# MODULES.net
KiCad netlist of a schematic drawn in Altium Designer
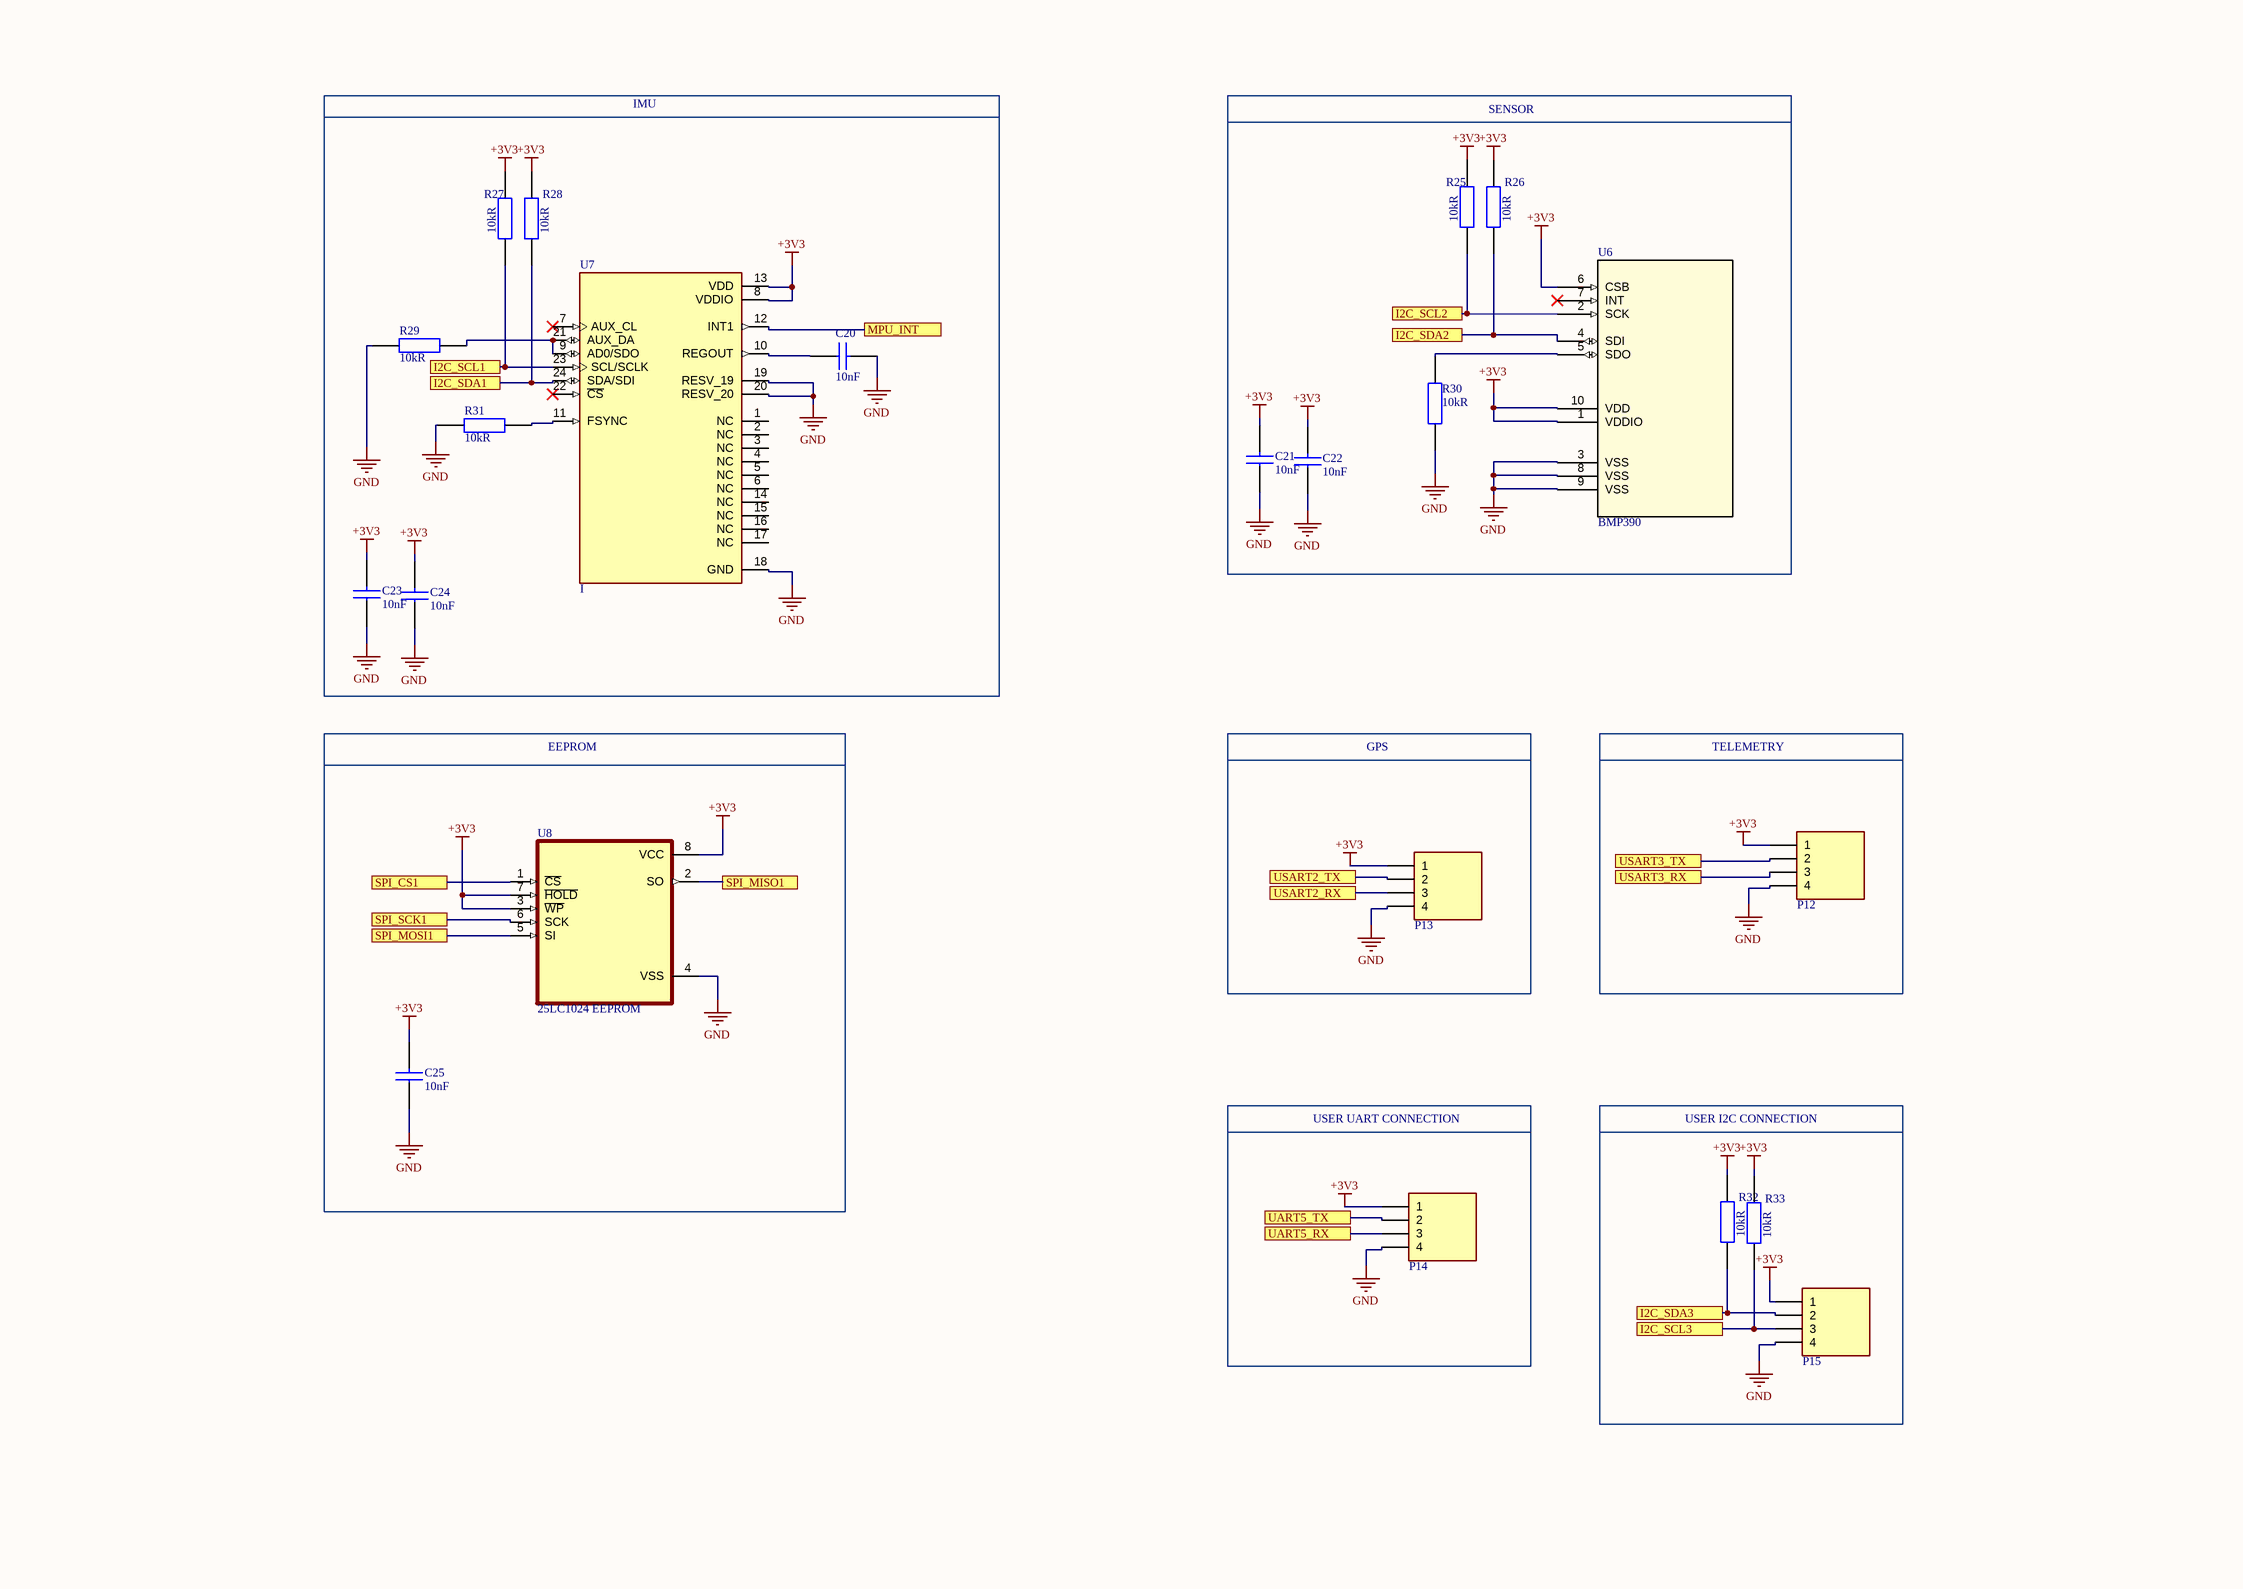
[diagram p0: MODULES.SchDoc]

(export (version "E")
  (design (tool "Eeschema 10.0.6"))
  (components
    (comp (ref "C20")
      (value "0603B103K160CT")
      (footprint "CAP_0603")
      (description "CAP CER 10nF %10 0603")
      (fields
        (field (name "MANUFACTURER") "Walsin Technologies")
        (field (name "TOLERANCE") "10%")
        (field (name "CAPACITANCE") "10nF")
        (field (name "DESIGNED BY") "BERK")
      )
      (libsource (lib "UDEMY_Library") (part "CAP CER 10nF 0603"))
    )
    (comp (ref "C21")
      (value "0603B103K160CT")
      (footprint "CAP_0603")
      (description "CAP CER 10nF %10 0603")
      (fields
        (field (name "MANUFACTURER") "Walsin Technologies")
        (field (name "TOLERANCE") "10%")
        (field (name "CAPACITANCE") "10nF")
        (field (name "DESIGNED BY") "BERK")
      )
      (libsource (lib "UDEMY_Library") (part "CAP CER 10nF 0603"))
    )
    (comp (ref "C22")
      (value "0603B103K160CT")
      (footprint "CAP_0603")
      (description "CAP CER 10nF %10 0603")
      (fields
        (field (name "MANUFACTURER") "Walsin Technologies")
        (field (name "TOLERANCE") "10%")
        (field (name "CAPACITANCE") "10nF")
        (field (name "DESIGNED BY") "BERK")
      )
      (libsource (lib "UDEMY_Library") (part "CAP CER 10nF 0603"))
    )
    (comp (ref "C23")
      (value "0603B103K160CT")
      (footprint "CAP_0603")
      (description "CAP CER 10nF %10 0603")
      (fields
        (field (name "MANUFACTURER") "Walsin Technologies")
        (field (name "TOLERANCE") "10%")
        (field (name "CAPACITANCE") "10nF")
        (field (name "DESIGNED BY") "BERK")
      )
      (libsource (lib "UDEMY_Library") (part "CAP CER 10nF 0603"))
    )
    (comp (ref "C24")
      (value "0603B103K160CT")
      (footprint "CAP_0603")
      (description "CAP CER 10nF %10 0603")
      (fields
        (field (name "MANUFACTURER") "Walsin Technologies")
        (field (name "TOLERANCE") "10%")
        (field (name "CAPACITANCE") "10nF")
        (field (name "DESIGNED BY") "BERK")
      )
      (libsource (lib "UDEMY_Library") (part "CAP CER 10nF 0603"))
    )
    (comp (ref "C25")
      (value "0603B103K160CT")
      (footprint "CAP_0603")
      (description "CAP CER 10nF %10 0603")
      (fields
        (field (name "MANUFACTURER") "Walsin Technologies")
        (field (name "TOLERANCE") "10%")
        (field (name "CAPACITANCE") "10nF")
        (field (name "DESIGNED BY") "BERK")
      )
      (libsource (lib "UDEMY_Library") (part "CAP CER 10nF 0603"))
    )
    (comp (ref "P12")
      (value "HEADER 4 PIN")
      (footprint "S4B-XH-A")
      (description "Header, Right Angle, 4Way; ¦Jst / Japan Solderless Terminals S4B-XH-A (LF)(SN)")
      (fields
        (field (name "MANUFACTURER") "JST")
        (field (name "MANUFACTURER PART NUMBER") "S4B-XH-A(LF)(SN)")
      )
      (libsource (lib "Main_Library") (part "HEADER 4 PIN"))
    )
    (comp (ref "P13")
      (value "HEADER 4 PIN")
      (footprint "S4B-XH-A")
      (description "Header, Right Angle, 4Way; ¦Jst / Japan Solderless Terminals S4B-XH-A (LF)(SN)")
      (fields
        (field (name "MANUFACTURER") "JST")
        (field (name "MANUFACTURER PART NUMBER") "S4B-XH-A(LF)(SN)")
      )
      (libsource (lib "Main_Library") (part "HEADER 4 PIN"))
    )
    (comp (ref "P14")
      (value "HEADER 4 PIN")
      (footprint "S4B-XH-A")
      (description "Header, Right Angle, 4Way; ¦Jst / Japan Solderless Terminals S4B-XH-A (LF)(SN)")
      (fields
        (field (name "MANUFACTURER") "JST")
        (field (name "MANUFACTURER PART NUMBER") "S4B-XH-A(LF)(SN)")
      )
      (libsource (lib "Main_Library") (part "HEADER 4 PIN"))
    )
    (comp (ref "P15")
      (value "HEADER 4 PIN")
      (footprint "S4B-XH-A")
      (description "Header, Right Angle, 4Way; ¦Jst / Japan Solderless Terminals S4B-XH-A (LF)(SN)")
      (fields
        (field (name "MANUFACTURER") "JST")
        (field (name "MANUFACTURER PART NUMBER") "S4B-XH-A(LF)(SN)")
      )
      (libsource (lib "Main_Library") (part "HEADER 4 PIN"))
    )
    (comp (ref "R25")
      (value "RC0603FR-0710KL")
      (footprint "RES_0603")
      (description "RES 10K %1 OHM 0603 SMD")
      (fields
        (field (name "MANUFACTURER") "Yageo")
        (field (name "TOLERANCE") "1%")
        (field (name "RESISTANCE") "10kR")
        (field (name "DESIGNED BY") "BERK")
      )
      (libsource (lib "UDEMY_Library") (part "RES 10K OHM 0603"))
    )
    (comp (ref "R26")
      (value "RC0603FR-0710KL")
      (footprint "RES_0603")
      (description "RES 10K %1 OHM 0603 SMD")
      (fields
        (field (name "MANUFACTURER") "Yageo")
        (field (name "TOLERANCE") "1%")
        (field (name "RESISTANCE") "10kR")
        (field (name "DESIGNED BY") "BERK")
      )
      (libsource (lib "UDEMY_Library") (part "RES 10K OHM 0603"))
    )
    (comp (ref "R27")
      (value "RC0603FR-0710KL")
      (footprint "RES_0603")
      (description "RES 10K %1 OHM 0603 SMD")
      (fields
        (field (name "MANUFACTURER") "Yageo")
        (field (name "TOLERANCE") "1%")
        (field (name "RESISTANCE") "10kR")
        (field (name "DESIGNED BY") "BERK")
      )
      (libsource (lib "UDEMY_Library") (part "RES 10K OHM 0603"))
    )
    (comp (ref "R28")
      (value "RC0603FR-0710KL")
      (footprint "RES_0603")
      (description "RES 10K %1 OHM 0603 SMD")
      (fields
        (field (name "MANUFACTURER") "Yageo")
        (field (name "TOLERANCE") "1%")
        (field (name "RESISTANCE") "10kR")
        (field (name "DESIGNED BY") "BERK")
      )
      (libsource (lib "UDEMY_Library") (part "RES 10K OHM 0603"))
    )
    (comp (ref "R29")
      (value "RC0603FR-0710KL")
      (footprint "RES_0603")
      (description "RES 10K %1 OHM 0603 SMD")
      (fields
        (field (name "MANUFACTURER") "Yageo")
        (field (name "TOLERANCE") "1%")
        (field (name "RESISTANCE") "10kR")
        (field (name "DESIGNED BY") "BERK")
      )
      (libsource (lib "") (part "RES 10K OHM 0603_1"))
    )
    (comp (ref "R30")
      (value "RC0603FR-0710KL")
      (footprint "RES_0603")
      (description "RES 10K %1 OHM 0603 SMD")
      (fields
        (field (name "MANUFACTURER") "Yageo")
        (field (name "TOLERANCE") "1%")
        (field (name "RESISTANCE") "10kR")
        (field (name "DESIGNED BY") "BERK")
      )
      (libsource (lib "UDEMY_Library") (part "RES 10K OHM 0603"))
    )
    (comp (ref "R31")
      (value "RC0603FR-0710KL")
      (footprint "RES_0603")
      (description "RES 10K %1 OHM 0603 SMD")
      (fields
        (field (name "MANUFACTURER") "Yageo")
        (field (name "TOLERANCE") "1%")
        (field (name "RESISTANCE") "10kR")
        (field (name "DESIGNED BY") "BERK")
      )
      (libsource (lib "") (part "RES 10K OHM 0603_1"))
    )
    (comp (ref "R32")
      (value "RC0603FR-0710KL")
      (footprint "RES_0603")
      (description "RES 10K %1 OHM 0603 SMD")
      (fields
        (field (name "MANUFACTURER") "Yageo")
        (field (name "TOLERANCE") "1%")
        (field (name "RESISTANCE") "10kR")
        (field (name "DESIGNED BY") "BERK")
      )
      (libsource (lib "UDEMY_Library") (part "RES 10K OHM 0603"))
    )
    (comp (ref "R33")
      (value "RC0603FR-0710KL")
      (footprint "RES_0603")
      (description "RES 10K %1 OHM 0603 SMD")
      (fields
        (field (name "MANUFACTURER") "Yageo")
        (field (name "TOLERANCE") "1%")
        (field (name "RESISTANCE") "10kR")
        (field (name "DESIGNED BY") "BERK")
      )
      (libsource (lib "UDEMY_Library") (part "RES 10K OHM 0603"))
    )
    (comp (ref "U6")
      (value "BMP390")
      (footprint "WFLGA-10")
      (description "3.0 Shuttle Board Dev Kit BMP390")
      (fields
        (field (name "MANUFACTURER") "Bosch Sensortec")
        (field (name "MANUFACTURER PART NUMBER") "SHUTTLE BOARD 3.0 BMP390")
      )
      (libsource (lib "Main_Library") (part "BMP390"))
    )
    (comp (ref "U7")
      (value "I")
      (footprint "TFQFN-24")
      (description "IMU (Inertial Measurement Unit), 9-Axis, Accelerometer, Gyroscope, Compass")
      (fields (field (name "MANUFACTURER") "TDK") (field (name "MANUFACTURER PART NUMBER") "ICM-20948"))
      (libsource (lib "Main_Library") (part "ICM-20948"))
    )
    (comp (ref "U8")
      (value "25LC1024 EEPROM")
      (footprint "SOIJ8")
      (description "SPI Serial EEPROM Family, 8-bit, 20 MHz, 2.5 to 5.5V, -40°Cto 125°C, SOIJ-8, RoHS")
      (fields
        (field (name "MANUFACTURER") "Microchip")
        (field (name "MANUFACTURER PART NUMBER") "25LC1024-E/SM")
      )
      (libsource (lib "Main_Library") (part "25LC1024 EEPROM"))
    )
  )
  (nets
    (net (code "1") (name "+3V3") (class "Default")
      (node (ref "C21") (pin "2") (pinfunction "2_2") (pintype "passive"))
      (node (ref "C22") (pin "2") (pinfunction "2_2") (pintype "passive"))
      (node (ref "C23") (pin "2") (pinfunction "2_2") (pintype "passive"))
      (node (ref "C24") (pin "2") (pinfunction "2_2") (pintype "passive"))
      (node (ref "C25") (pin "2") (pinfunction "2_2") (pintype "passive"))
      (node (ref "P12") (pin "1") (pinfunction "1_1") (pintype "passive"))
      (node (ref "P13") (pin "1") (pinfunction "1_1") (pintype "passive"))
      (node (ref "P14") (pin "1") (pinfunction "1_1") (pintype "passive"))
      (node (ref "P15") (pin "1") (pinfunction "1_1") (pintype "passive"))
      (node (ref "R25") (pin "2") (pinfunction "2_2") (pintype "passive"))
      (node (ref "R26") (pin "2") (pinfunction "2_2") (pintype "passive"))
      (node (ref "R27") (pin "2") (pinfunction "2_2") (pintype "passive"))
      (node (ref "R28") (pin "2") (pinfunction "2_2") (pintype "passive"))
      (node (ref "R32") (pin "2") (pinfunction "2_2") (pintype "passive"))
      (node (ref "R33") (pin "2") (pinfunction "2_2") (pintype "passive"))
      (node (ref "U6") (pin "1") (pinfunction "VDDIO_1") (pintype "power_in"))
      (node (ref "U6") (pin "10") (pinfunction "VDD_10") (pintype "power_in"))
      (node (ref "U6") (pin "6") (pinfunction "CSB_6") (pintype "input"))
      (node (ref "U7") (pin "13") (pinfunction "VDD_13") (pintype "power_in"))
      (node (ref "U7") (pin "8") (pinfunction "VDDIO_8") (pintype "power_in"))
      (node (ref "U8") (pin "3") (pinfunction "~{WP}_3") (pintype "input"))
      (node (ref "U8") (pin "7") (pinfunction "~{HOLD}_7") (pintype "input"))
      (node (ref "U8") (pin "8") (pinfunction "VCC_8") (pintype "power_in"))
    )
    (net (code "2") (name "/I2C_SCL1") (class "Default")
      (node (ref "R27") (pin "1") (pinfunction "1_1") (pintype "passive"))
      (node (ref "U7") (pin "23") (pinfunction "SCL/SCLK_23") (pintype "input"))
    )
    (net (code "3") (name "/I2C_SCL2") (class "Default")
      (node (ref "R25") (pin "1") (pinfunction "1_1") (pintype "passive"))
      (node (ref "U6") (pin "2") (pinfunction "SCK_2") (pintype "input"))
    )
    (net (code "4") (name "/I2C_SCL3") (class "Default")
      (node (ref "P15") (pin "3") (pinfunction "3_3") (pintype "passive"))
      (node (ref "R33") (pin "1") (pinfunction "1_1") (pintype "passive"))
    )
    (net (code "5") (name "/I2C_SDA1") (class "Default")
      (node (ref "R28") (pin "1") (pinfunction "1_1") (pintype "passive"))
      (node (ref "U7") (pin "24") (pinfunction "SDA/SDI_24") (pintype "bidirectional"))
    )
    (net (code "6") (name "/I2C_SDA2") (class "Default")
      (node (ref "R26") (pin "1") (pinfunction "1_1") (pintype "passive"))
      (node (ref "U6") (pin "4") (pinfunction "SDI_4") (pintype "bidirectional"))
    )
    (net (code "7") (name "/I2C_SDA3") (class "Default")
      (node (ref "P15") (pin "2") (pinfunction "2_2") (pintype "passive"))
      (node (ref "R32") (pin "1") (pinfunction "1_1") (pintype "passive"))
    )
    (net (code "8") (name "/MPU_INT") (class "Default")
      (node (ref "U7") (pin "12") (pinfunction "INT1_12") (pintype "output"))
    )
    (net (code "9") (name "/SPI_CS1") (class "Default")
      (node (ref "U8") (pin "1") (pinfunction "~{CS}_1") (pintype "input"))
    )
    (net (code "10") (name "/SPI_MISO1") (class "Default")
      (node (ref "U8") (pin "2") (pinfunction "SO_2") (pintype "output"))
    )
    (net (code "11") (name "/SPI_MOSI1") (class "Default")
      (node (ref "U8") (pin "5") (pinfunction "SI_5") (pintype "input"))
    )
    (net (code "12") (name "/SPI_SCK1") (class "Default")
      (node (ref "U8") (pin "6") (pinfunction "SCK_6") (pintype "input"))
    )
    (net (code "13") (name "/UART5_RX") (class "Default")
      (node (ref "P14") (pin "3") (pinfunction "3_3") (pintype "passive"))
    )
    (net (code "14") (name "/UART5_TX") (class "Default")
      (node (ref "P14") (pin "2") (pinfunction "2_2") (pintype "passive"))
    )
    (net (code "15") (name "/USART2_RX") (class "Default")
      (node (ref "P13") (pin "3") (pinfunction "3_3") (pintype "passive"))
    )
    (net (code "16") (name "/USART2_TX") (class "Default")
      (node (ref "P13") (pin "2") (pinfunction "2_2") (pintype "passive"))
    )
    (net (code "17") (name "/USART3_RX") (class "Default")
      (node (ref "P12") (pin "3") (pinfunction "3_3") (pintype "passive"))
    )
    (net (code "18") (name "/USART3_TX") (class "Default")
      (node (ref "P12") (pin "2") (pinfunction "2_2") (pintype "passive"))
    )
    (net (code "19") (name "GND") (class "Default")
      (node (ref "C20") (pin "2") (pinfunction "2_2") (pintype "passive"))
      (node (ref "C21") (pin "1") (pinfunction "1_1") (pintype "passive"))
      (node (ref "C22") (pin "1") (pinfunction "1_1") (pintype "passive"))
      (node (ref "C23") (pin "1") (pinfunction "1_1") (pintype "passive"))
      (node (ref "C24") (pin "1") (pinfunction "1_1") (pintype "passive"))
      (node (ref "C25") (pin "1") (pinfunction "1_1") (pintype "passive"))
      (node (ref "P12") (pin "4") (pinfunction "4_4") (pintype "passive"))
      (node (ref "P13") (pin "4") (pinfunction "4_4") (pintype "passive"))
      (node (ref "P14") (pin "4") (pinfunction "4_4") (pintype "passive"))
      (node (ref "P15") (pin "4") (pinfunction "4_4") (pintype "passive"))
      (node (ref "R29") (pin "1") (pinfunction "1_1") (pintype "passive"))
      (node (ref "R30") (pin "1") (pinfunction "1_1") (pintype "passive"))
      (node (ref "R31") (pin "1") (pinfunction "1_1") (pintype "passive"))
      (node (ref "U6") (pin "3") (pinfunction "VSS_3") (pintype "power_in"))
      (node (ref "U6") (pin "8") (pinfunction "VSS_8") (pintype "power_in"))
      (node (ref "U6") (pin "9") (pinfunction "VSS_9") (pintype "power_in"))
      (node (ref "U7") (pin "18") (pinfunction "GND_18") (pintype "power_in"))
      (node (ref "U7") (pin "19") (pinfunction "RESV_19_19") (pintype "passive"))
      (node (ref "U7") (pin "20") (pinfunction "RESV_20_20") (pintype "passive"))
      (node (ref "U8") (pin "4") (pinfunction "VSS_4") (pintype "power_in"))
    )
    (net (code "20") (name "Net-(U6-SDO)") (class "Default")
      (node (ref "R30") (pin "2") (pinfunction "2_2") (pintype "passive"))
      (node (ref "U6") (pin "5") (pinfunction "SDO_5") (pintype "bidirectional"))
    )
    (net (code "21") (name "Net-(U7-AD0{slash}SDO)") (class "Default")
      (node (ref "R29") (pin "2") (pinfunction "2_2") (pintype "passive"))
      (node (ref "U7") (pin "21") (pinfunction "AUX_DA_21") (pintype "bidirectional"))
      (node (ref "U7") (pin "9") (pinfunction "AD0/SDO_9") (pintype "bidirectional"))
    )
    (net (code "22") (name "Net-(U7-FSYNC)") (class "Default")
      (node (ref "R31") (pin "2") (pinfunction "2_2") (pintype "passive"))
      (node (ref "U7") (pin "11") (pinfunction "FSYNC_11") (pintype "input"))
    )
    (net (code "23") (name "Net-(U7-REGOUT)") (class "Default")
      (node (ref "C20") (pin "1") (pinfunction "1_1") (pintype "passive"))
      (node (ref "U7") (pin "10") (pinfunction "REGOUT_10") (pintype "output"))
    )
    (net (code "24") (name "unconnected-(U6-INT-Pad7)") (class "Default")
      (node (ref "U6") (pin "7") (pinfunction "INT_7") (pintype "input+no_connect"))
    )
    (net (code "25") (name "unconnected-(U7-AUX_CL-Pad7)") (class "Default")
      (node (ref "U7") (pin "7") (pinfunction "AUX_CL_7") (pintype "input+no_connect"))
    )
    (net (code "26") (name "unconnected-(U7-NC-Pad1)") (class "Default")
      (node (ref "U7") (pin "1") (pinfunction "NC_1") (pintype "passive"))
    )
    (net (code "27") (name "unconnected-(U7-NC-Pad2)") (class "Default")
      (node (ref "U7") (pin "2") (pinfunction "NC_2") (pintype "passive"))
    )
    (net (code "28") (name "unconnected-(U7-NC-Pad3)") (class "Default")
      (node (ref "U7") (pin "3") (pinfunction "NC_3") (pintype "passive"))
    )
    (net (code "29") (name "unconnected-(U7-NC-Pad4)") (class "Default")
      (node (ref "U7") (pin "4") (pinfunction "NC_4") (pintype "passive"))
    )
    (net (code "30") (name "unconnected-(U7-NC-Pad5)") (class "Default")
      (node (ref "U7") (pin "5") (pinfunction "NC_5") (pintype "passive"))
    )
    (net (code "31") (name "unconnected-(U7-NC-Pad6)") (class "Default")
      (node (ref "U7") (pin "6") (pinfunction "NC_6") (pintype "passive"))
    )
    (net (code "32") (name "unconnected-(U7-NC-Pad14)") (class "Default")
      (node (ref "U7") (pin "14") (pinfunction "NC_14") (pintype "passive"))
    )
    (net (code "33") (name "unconnected-(U7-NC-Pad15)") (class "Default")
      (node (ref "U7") (pin "15") (pinfunction "NC_15") (pintype "passive"))
    )
    (net (code "34") (name "unconnected-(U7-NC-Pad16)") (class "Default")
      (node (ref "U7") (pin "16") (pinfunction "NC_16") (pintype "passive"))
    )
    (net (code "35") (name "unconnected-(U7-NC-Pad17)") (class "Default")
      (node (ref "U7") (pin "17") (pinfunction "NC_17") (pintype "passive"))
    )
    (net (code "36") (name "unconnected-(U7-~{CS}-Pad22)") (class "Default")
      (node (ref "U7") (pin "22") (pinfunction "~{CS}_22") (pintype "input+no_connect"))
    )
  )
)
